# CoolerUI_SCH.net
KiCad netlist of a schematic drawn in Altium Designer
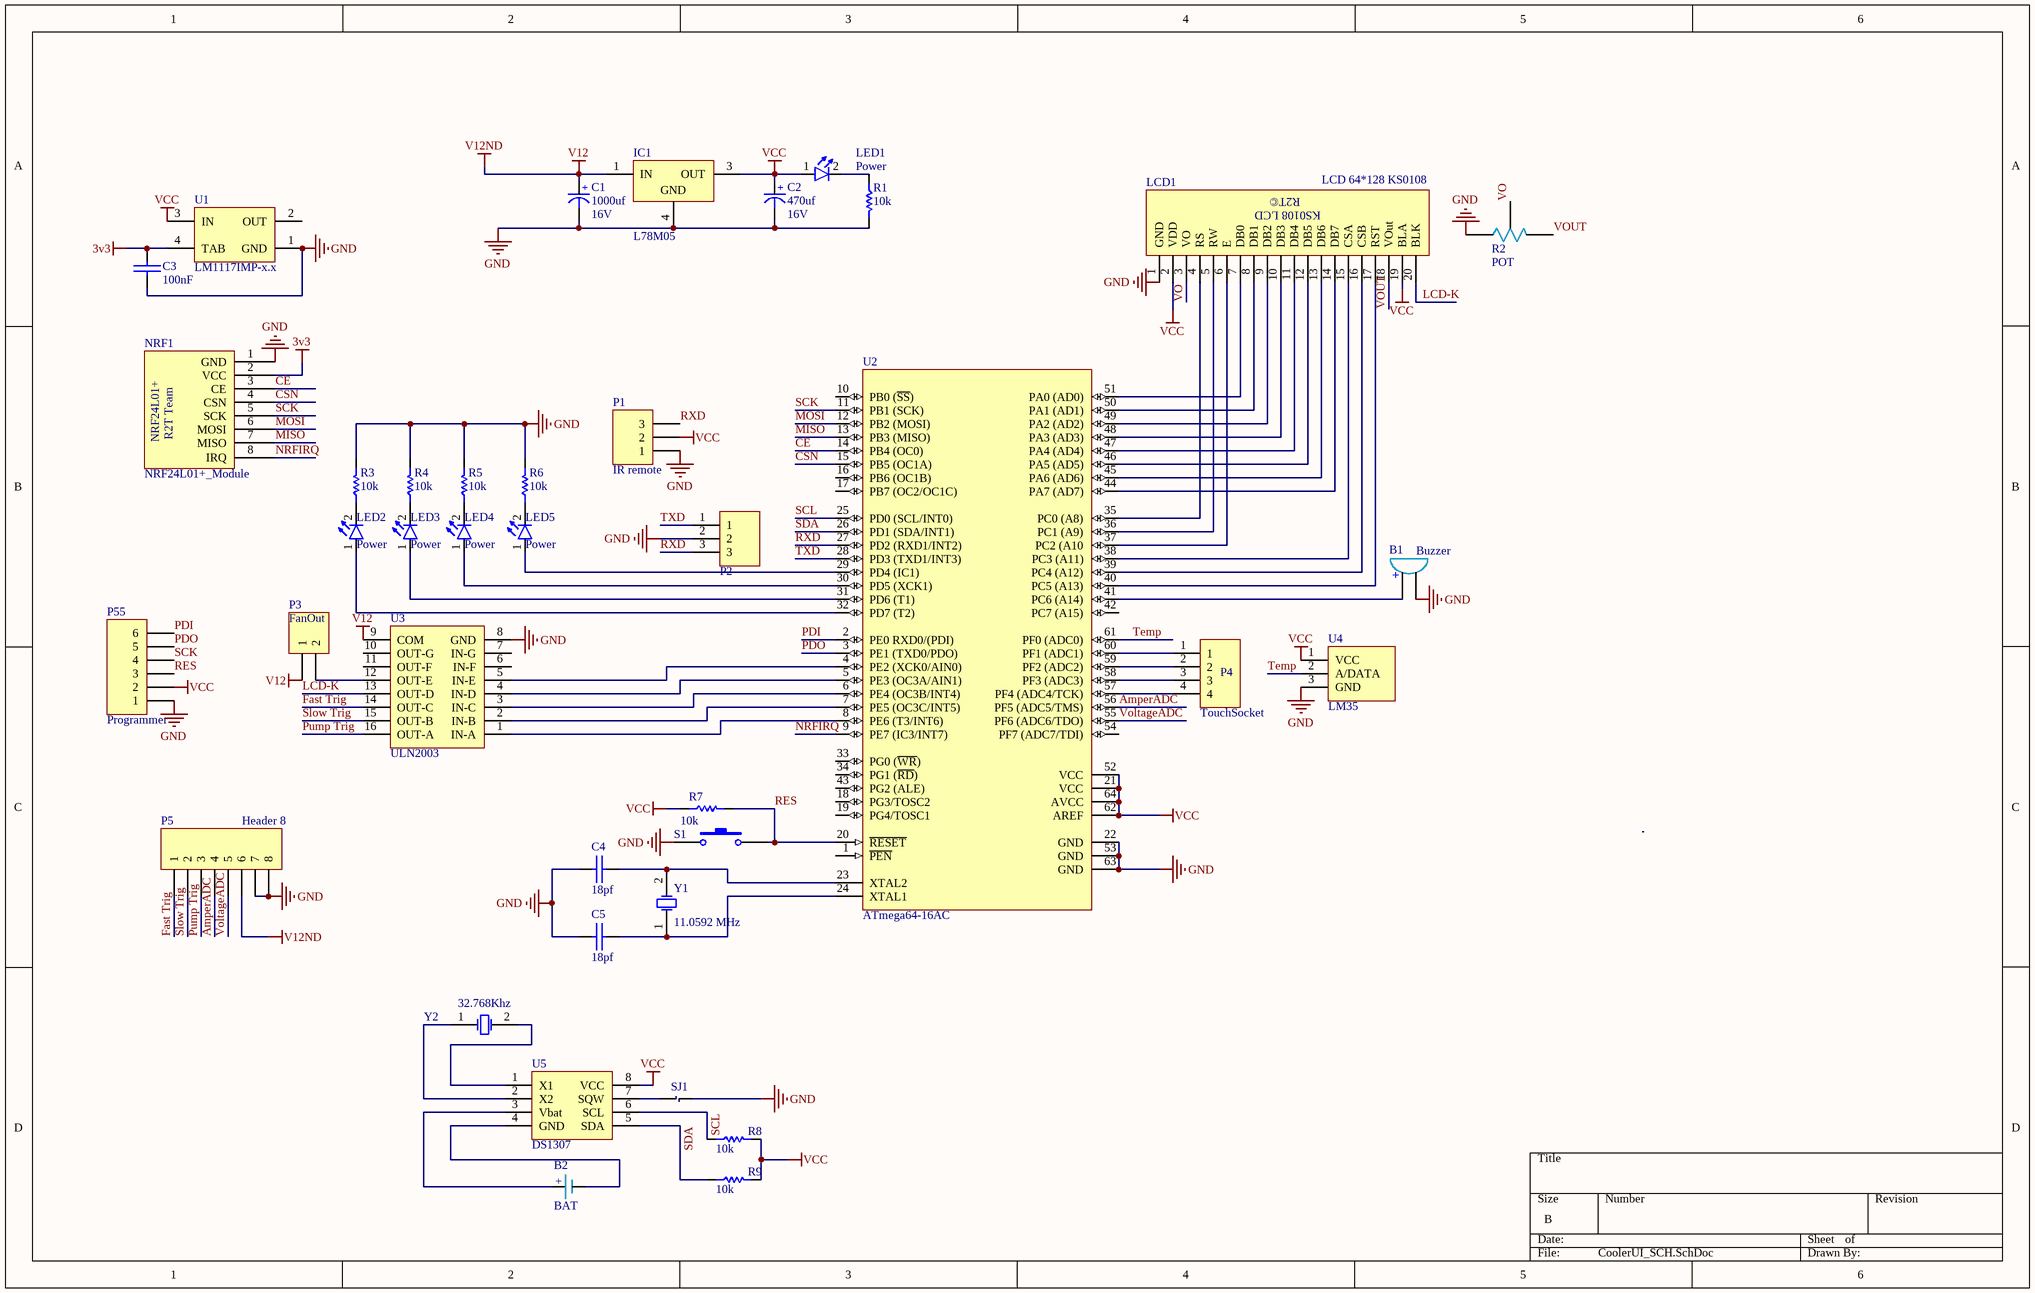
[diagram p0: CoolerUI_SCH.SchDoc]

(export (version "E")
  (design (tool "Eeschema 10.0.6"))
  (components
    (comp (ref "B1")
      (value "Buzzer")
      (footprint "Buzzer")
      (fields (field (name "DESIGNER") "Hamed Jafarzadeh"))
      (libsource (lib "R2T Team Library") (part "Buzzer"))
    )
    (comp (ref "B2") (value "BAT") (footprint "BAT_H") (libsource (lib "My_lib_new") (part "BAT")))
    (comp (ref "C1")
      (value "1000uf")
      (footprint "cap 04")
      (description "Polar Capacitor")
      (fields (field (name "VOLTAGE") "16V") (field (name "DESIGNER") "Saeid Jorablo"))
      (libsource (lib "My Library") (part "Cap-Polar"))
    )
    (comp (ref "C2")
      (value "470uf")
      (footprint "cap 03")
      (description "Polar Capacitor")
      (fields (field (name "VOLTAGE") "16V") (field (name "DESIGNER") "Saeid Jorablo"))
      (libsource (lib "My Library") (part "Cap-Polar"))
    )
    (comp (ref "C3")
      (value "100nF")
      (footprint "SMD_CAP_1206")
      (description "Bipolar Capacitor")
      (fields (field (name "VOLTAGE") "100V") (field (name "DESIGNER") "Saeid Jorablo"))
      (libsource (lib "My Library") (part "Cap-Bipolar"))
    )
    (comp (ref "C4")
      (value "18pf")
      (footprint "SMD_CAP_0805")
      (description "Bipolar Capacitor")
      (fields (field (name "VOLTAGE") "100V") (field (name "DESIGNER") "Saeid Jorablo"))
      (libsource (lib "My Library") (part "Cap-Bipolar"))
    )
    (comp (ref "C5")
      (value "18pf")
      (footprint "SMD_CAP_0805")
      (description "Bipolar Capacitor")
      (fields (field (name "VOLTAGE") "100V") (field (name "DESIGNER") "Saeid Jorablo"))
      (libsource (lib "My Library") (part "Cap-Bipolar"))
    )
    (comp (ref "IC1")
      (value "L78M05")
      (footprint "TO-252")
      (description "Precision 500mA Regulator")
      (libsource (lib "My Library") (part "L78M05"))
    )
    (comp (ref "LCD1")
      (value "LCD 64*128 KS0108")
      (footprint "KS0108 Graphical LCD")
      (libsource (lib "R2T Team Library") (part "LCD 64*128 KS0108"))
    )
    (comp (ref "LED1")
      (value "Power")
      (footprint "LED SMD 1206")
      (description "LED")
      (fields (field (name "COLOR") "Power") (field (name "DESIGNER") "Saeid Jorablo"))
      (libsource (lib "My Library") (part "LED"))
    )
    (comp (ref "LED2")
      (value "Power")
      (footprint "LED SMD 1206")
      (description "LED")
      (fields (field (name "COLOR") "Power") (field (name "DESIGNER") "Saeid Jorablo"))
      (libsource (lib "My Library") (part "LED"))
    )
    (comp (ref "LED3")
      (value "Power")
      (footprint "LED SMD 1206")
      (description "LED")
      (fields (field (name "COLOR") "Power") (field (name "DESIGNER") "Saeid Jorablo"))
      (libsource (lib "My Library") (part "LED"))
    )
    (comp (ref "LED4")
      (value "Power")
      (footprint "LED SMD 1206")
      (description "LED")
      (fields (field (name "COLOR") "Power") (field (name "DESIGNER") "Saeid Jorablo"))
      (libsource (lib "My Library") (part "LED"))
    )
    (comp (ref "LED5")
      (value "Power")
      (footprint "LED SMD 1206")
      (description "LED")
      (fields (field (name "COLOR") "Power") (field (name "DESIGNER") "Saeid Jorablo"))
      (libsource (lib "My Library") (part "LED"))
    )
    (comp (ref "NRF1")
      (value "NRF24L01+_Module")
      (footprint "NRF24L01+_Module")
      (fields (field (name "DESIGNER:") "HamedJafarzadeh"))
      (libsource (lib "R2T Team Library") (part "NRF24L01+_Module"))
    )
    (comp (ref "P1")
      (value "IR remote")
      (footprint "HDR1X3")
      (description "Header, 3-Pin")
      (fields (field (name "PUBLISHER") "Altium Limited"))
      (libsource (lib "Miscellaneous Connectors") (part "Header 3"))
    )
    (comp (ref "P2")
      (value "HWR")
      (footprint "Polarized Header 3")
      (fields (field (name "DESIGNER:") "Hamed Jafarzadeh - www.R2T.ir"))
      (libsource (lib "R2T Team Library") (part "3pin LHWR"))
    )
    (comp (ref "P3")
      (value "FanOut")
      (footprint "HDR1X2")
      (description "Header, 2-Pin")
      (fields (field (name "PUBLISHER") "Altium Limited"))
      (libsource (lib "Miscellaneous Connectors") (part "Header 2"))
    )
    (comp (ref "P4")
      (value "TouchSocket")
      (footprint "FPC,1mm,4way")
      (libsource (lib "R2T Team Library") (part "Header FPC 4pin"))
    )
    (comp (ref "P5")
      (value "Header 8")
      (footprint "HDR1X8")
      (description "Header, 8-Pin")
      (fields (field (name "PUBLISHER") "Altium Limited"))
      (libsource (lib "Miscellaneous Connectors") (part "Header 8"))
    )
    (comp (ref "P55")
      (value "Programmer")
      (footprint "HDR1X6")
      (description "Header, 6-Pin")
      (fields (field (name "PUBLISHER") "Altium Limited"))
      (libsource (lib "Miscellaneous Connectors") (part "Header 6"))
    )
    (comp (ref "R1")
      (value "10k")
      (footprint "RES 0805 (2012X06L)")
      (description "Resistor")
      (fields (field (name "TOLERANCE") "5%") (field (name "POWER") "1/8 W"))
      (libsource (lib "My Library") (part "Resistor"))
    )
    (comp (ref "R2") (value "POT") (footprint "MOL_1") (libsource (lib "My_lib_new") (part "POT")))
    (comp (ref "R3")
      (value "10k")
      (footprint "RES 0805 (2012X06L)")
      (description "Resistor")
      (fields (field (name "TOLERANCE") "5%") (field (name "POWER") "1/8 W"))
      (libsource (lib "My Library") (part "Resistor"))
    )
    (comp (ref "R4")
      (value "10k")
      (footprint "RES 0805 (2012X06L)")
      (description "Resistor")
      (fields (field (name "TOLERANCE") "5%") (field (name "POWER") "1/8 W"))
      (libsource (lib "My Library") (part "Resistor"))
    )
    (comp (ref "R5")
      (value "10k")
      (footprint "RES 0805 (2012X06L)")
      (description "Resistor")
      (fields (field (name "TOLERANCE") "5%") (field (name "POWER") "1/8 W"))
      (libsource (lib "My Library") (part "Resistor"))
    )
    (comp (ref "R6")
      (value "10k")
      (footprint "RES 0805 (2012X06L)")
      (description "Resistor")
      (fields (field (name "TOLERANCE") "5%") (field (name "POWER") "1/8 W"))
      (libsource (lib "My Library") (part "Resistor"))
    )
    (comp (ref "R7")
      (value "10k")
      (footprint "RES 0805 (2012X06L)")
      (description "Resistor")
      (fields (field (name "TOLERANCE") "5%") (field (name "POWER") "1/8 W"))
      (libsource (lib "My Library") (part "Resistor"))
    )
    (comp (ref "R8")
      (value "10k")
      (footprint "RES 0805 (2012X06L)")
      (description "Resistor")
      (libsource (lib "My Library") (part "Resistor"))
    )
    (comp (ref "R9")
      (value "10k")
      (footprint "RES 0805 (2012X06L)")
      (description "Resistor")
      (libsource (lib "My Library") (part "Resistor"))
    )
    (comp (ref "S1")
      (value "Switch PB SMD")
      (footprint "Switch PB SMD")
      (libsource (lib "R2T Team Library") (part "Switch PB SMD"))
    )
    (comp (ref "SJ1")
      (value "SmdJumper")
      (footprint "SMD Jumper")
      (libsource (lib "R2T Team Library") (part "SmdJumper"))
    )
    (comp (ref "U1")
      (value "LM1117IMP-x.x")
      (footprint "MP04A_N")
      (description "x.x Volt, 800mA Low-Dropout Linear Regulator, 4-pin SOT-223")
      (fields
        (field (name "PARTNUMBER") "LM1117IMP-3.3")
        (field (name "MANUFACTURER") "National Semiconductor")
        (field (name "PUBLISHER") "Altium Limited")
      )
      (libsource (lib "My Library") (part "LM1117IMP-x.x"))
    )
    (comp (ref "U2")
      (value "ATmega64-16AC")
      (footprint "64A_N")
      (description "8-Bit AVR Microcontroller with 64K Bytes of In-System Programmable Flash Memory")
      (fields (field (name "PUBLISHER") "Altium Limited"))
      (libsource (lib "Atmel Microcontroller 8-Bit AVR") (part "ATmega64-16AC"))
    )
    (comp (ref "U3") (value "ULN2003") (footprint "SO-16") (libsource (lib "My_lib_new") (part "ULN2003")))
    (comp (ref "U4") (value "LM35") (footprint "LM35") (libsource (lib "My_lib_new") (part "LM35")))
    (comp (ref "U5") (value "DS1307") (footprint "DIP8") (libsource (lib "My_lib_new") (part "DS1307")))
    (comp (ref "Y1")
      (value "11.0592 MHz")
      (footprint "Crystal SMD")
      (description "XTAL Crystal")
      (libsource (lib "My Library") (part "XTAL"))
    )
    (comp (ref "Y2")
      (value "32.768Khz")
      (footprint "XTAL RTC")
      (description "XTAL Crystal")
      (libsource (lib "My Library") (part "XTAL"))
    )
  )
  (nets
    (net (code "1") (name "/AmperADC") (class "Default")
      (node (ref "P5") (pin "4") (pinfunction "4_4") (pintype "passive"))
      (node (ref "U2") (pin "56") (pinfunction "PF5_(ADC5/TMS)_56") (pintype "bidirectional"))
    )
    (net (code "2") (name "/CE") (class "Default")
      (node (ref "NRF1") (pin "3") (pinfunction "CE_3") (pintype "passive"))
      (node (ref "U2") (pin "14") (pinfunction "PB4_(OC0)_14") (pintype "bidirectional"))
    )
    (net (code "3") (name "/CSN") (class "Default")
      (node (ref "NRF1") (pin "4") (pinfunction "CSN_4") (pintype "passive"))
      (node (ref "U2") (pin "15") (pinfunction "PB5_(OC1A)_15") (pintype "bidirectional"))
    )
    (net (code "4") (name "/Fast Trig") (class "Default")
      (node (ref "P5") (pin "1") (pinfunction "1_1") (pintype "passive"))
      (node (ref "U3") (pin "14") (pinfunction "OUT-C_14") (pintype "passive"))
    )
    (net (code "5") (name "/LCD-K") (class "Default")
      (node (ref "LCD1") (pin "20") (pinfunction "BLK_20") (pintype "passive"))
      (node (ref "U3") (pin "13") (pinfunction "OUT-D_13") (pintype "passive"))
    )
    (net (code "6") (name "/MISO") (class "Default")
      (node (ref "NRF1") (pin "7") (pinfunction "MISO_7") (pintype "passive"))
      (node (ref "U2") (pin "13") (pinfunction "PB3_(MISO)_13") (pintype "bidirectional"))
    )
    (net (code "7") (name "/MOSI") (class "Default")
      (node (ref "NRF1") (pin "6") (pinfunction "MOSI_6") (pintype "passive"))
      (node (ref "U2") (pin "12") (pinfunction "PB2_(MOSI)_12") (pintype "bidirectional"))
    )
    (net (code "8") (name "/NRFIRQ") (class "Default")
      (node (ref "NRF1") (pin "8") (pinfunction "IRQ_8") (pintype "passive"))
      (node (ref "U2") (pin "9") (pinfunction "PE7_(IC3/INT7)_9") (pintype "bidirectional"))
    )
    (net (code "9") (name "/PDI") (class "Default")
      (node (ref "P55") (pin "6") (pinfunction "6_6") (pintype "passive"))
      (node (ref "U2") (pin "2") (pinfunction "PE0_RXD0/(PDI)_2") (pintype "bidirectional"))
    )
    (net (code "10") (name "/PDO") (class "Default")
      (node (ref "P55") (pin "5") (pinfunction "5_5") (pintype "passive"))
      (node (ref "U2") (pin "3") (pinfunction "PE1_(TXD0/PDO)_3") (pintype "bidirectional"))
    )
    (net (code "11") (name "/Pump Trig") (class "Default")
      (node (ref "P5") (pin "3") (pinfunction "3_3") (pintype "passive"))
      (node (ref "U3") (pin "16") (pinfunction "OUT-A_16") (pintype "passive"))
    )
    (net (code "12") (name "/RES") (class "Default")
      (node (ref "P55") (pin "3") (pinfunction "3_3") (pintype "passive"))
      (node (ref "R7") (pin "2") (pinfunction "2_2") (pintype "passive"))
      (node (ref "S1") (pin "2") (pinfunction "2_2") (pintype "passive"))
      (node (ref "U2") (pin "20") (pinfunction "~{RESET}_20") (pintype "input"))
    )
    (net (code "13") (name "/RXD") (class "Default")
      (node (ref "P1") (pin "3") (pinfunction "3_3") (pintype "passive"))
      (node (ref "P2") (pin "3") (pinfunction "3_3") (pintype "passive"))
      (node (ref "U2") (pin "27") (pinfunction "PD2_(RXD1/INT2)_27") (pintype "bidirectional"))
    )
    (net (code "14") (name "/SCK") (class "Default")
      (node (ref "NRF1") (pin "5") (pinfunction "SCK_5") (pintype "passive"))
      (node (ref "P55") (pin "4") (pinfunction "4_4") (pintype "passive"))
      (node (ref "U2") (pin "11") (pinfunction "PB1_(SCK)_11") (pintype "bidirectional"))
    )
    (net (code "15") (name "/SCL") (class "Default")
      (node (ref "R8") (pin "1") (pinfunction "1_1") (pintype "passive"))
      (node (ref "U2") (pin "25") (pinfunction "PD0_(SCL/INT0)_25") (pintype "bidirectional"))
      (node (ref "U5") (pin "6") (pinfunction "SCL_6") (pintype "passive"))
    )
    (net (code "16") (name "/SDA") (class "Default")
      (node (ref "R9") (pin "1") (pinfunction "1_1") (pintype "passive"))
      (node (ref "U2") (pin "26") (pinfunction "PD1_(SDA/INT1)_26") (pintype "bidirectional"))
      (node (ref "U5") (pin "5") (pinfunction "SDA_5") (pintype "passive"))
    )
    (net (code "17") (name "/Slow Trig") (class "Default")
      (node (ref "P5") (pin "2") (pinfunction "2_2") (pintype "passive"))
      (node (ref "U3") (pin "15") (pinfunction "OUT-B_15") (pintype "passive"))
    )
    (net (code "18") (name "/TXD") (class "Default")
      (node (ref "P2") (pin "1") (pinfunction "1_1") (pintype "passive"))
      (node (ref "U2") (pin "28") (pinfunction "PD3_(TXD1/INT3)_28") (pintype "bidirectional"))
    )
    (net (code "19") (name "/Temp") (class "Default")
      (node (ref "U2") (pin "61") (pinfunction "PF0_(ADC0)_61") (pintype "bidirectional"))
      (node (ref "U4") (pin "2") (pinfunction "A/DATA_2") (pintype "passive"))
    )
    (net (code "20") (name "/VO") (class "Default")
      (node (ref "LCD1") (pin "3") (pinfunction "VO_3") (pintype "passive"))
      (node (ref "R2") (pin "2") (pintype "passive"))
    )
    (net (code "21") (name "/VOUT") (class "Default")
      (node (ref "LCD1") (pin "18") (pinfunction "VOut_18") (pintype "passive"))
      (node (ref "R2") (pin "3") (pintype "passive"))
    )
    (net (code "22") (name "/VoltageADC") (class "Default")
      (node (ref "P5") (pin "5") (pinfunction "5_5") (pintype "passive"))
      (node (ref "U2") (pin "55") (pinfunction "PF6_(ADC6/TDO)_55") (pintype "bidirectional"))
    )
    (net (code "23") (name "3v3") (class "Default")
      (node (ref "C3") (pin "1") (pinfunction "+_1") (pintype "passive"))
      (node (ref "NRF1") (pin "2") (pinfunction "VCC_2") (pintype "passive"))
      (node (ref "U1") (pin "4") (pinfunction "TAB_4") (pintype "power_in"))
    )
    (net (code "24") (name "GND") (class "Default")
      (node (ref "B1") (pin "2") (pinfunction "GND_2") (pintype "passive"))
      (node (ref "C1") (pin "2") (pinfunction "-_2") (pintype "passive"))
      (node (ref "C2") (pin "2") (pinfunction "-_2") (pintype "passive"))
      (node (ref "C3") (pin "2") (pinfunction "-_2") (pintype "passive"))
      (node (ref "C4") (pin "1") (pinfunction "+_1") (pintype "passive"))
      (node (ref "C5") (pin "1") (pinfunction "+_1") (pintype "passive"))
      (node (ref "IC1") (pin "4") (pinfunction "GND_4") (pintype "power_in"))
      (node (ref "LCD1") (pin "1") (pinfunction "GND_1") (pintype "passive"))
      (node (ref "NRF1") (pin "1") (pinfunction "GND_1") (pintype "passive"))
      (node (ref "P1") (pin "1") (pinfunction "1_1") (pintype "passive"))
      (node (ref "P2") (pin "2") (pinfunction "2_2") (pintype "passive"))
      (node (ref "P5") (pin "7") (pinfunction "7_7") (pintype "passive"))
      (node (ref "P5") (pin "8") (pinfunction "8_8") (pintype "passive"))
      (node (ref "P55") (pin "1") (pinfunction "1_1") (pintype "passive"))
      (node (ref "R1") (pin "2") (pinfunction "2_2") (pintype "passive"))
      (node (ref "R2") (pin "1") (pintype "passive"))
      (node (ref "R3") (pin "2") (pinfunction "2_2") (pintype "passive"))
      (node (ref "R4") (pin "2") (pinfunction "2_2") (pintype "passive"))
      (node (ref "R5") (pin "2") (pinfunction "2_2") (pintype "passive"))
      (node (ref "R6") (pin "2") (pinfunction "2_2") (pintype "passive"))
      (node (ref "S1") (pin "1") (pinfunction "1_1") (pintype "passive"))
      (node (ref "SJ1") (pin "2") (pinfunction "2_2") (pintype "passive"))
      (node (ref "U1") (pin "1") (pinfunction "GND_1") (pintype "power_in"))
      (node (ref "U2") (pin "22") (pinfunction "GND_22") (pintype "power_in"))
      (node (ref "U2") (pin "53") (pinfunction "GND_53") (pintype "power_in"))
      (node (ref "U2") (pin "63") (pinfunction "GND_63") (pintype "power_in"))
      (node (ref "U3") (pin "8") (pinfunction "GND_8") (pintype "passive"))
      (node (ref "U4") (pin "3") (pinfunction "GND_3") (pintype "passive"))
    )
    (net (code "25") (name "Net-(B1-VCC)") (class "Default")
      (node (ref "B1") (pin "1") (pinfunction "VCC_1") (pintype "passive"))
      (node (ref "U2") (pin "41") (pinfunction "PC6_(A14)_41") (pintype "bidirectional"))
    )
    (net (code "26") (name "Net-(C4--)") (class "Default")
      (node (ref "C4") (pin "2") (pinfunction "-_2") (pintype "passive"))
      (node (ref "U2") (pin "23") (pinfunction "XTAL2_23") (pintype "passive"))
      (node (ref "Y1") (pin "2") (pinfunction "OSC2_2") (pintype "passive"))
    )
    (net (code "27") (name "Net-(C5--)") (class "Default")
      (node (ref "C5") (pin "2") (pinfunction "-_2") (pintype "passive"))
      (node (ref "U2") (pin "24") (pinfunction "XTAL1_24") (pintype "passive"))
      (node (ref "Y1") (pin "1") (pinfunction "OSC1_1") (pintype "passive"))
    )
    (net (code "28") (name "Net-(LCD1-CSA)") (class "Default")
      (node (ref "LCD1") (pin "15") (pinfunction "CSA_15") (pintype "passive"))
      (node (ref "U2") (pin "38") (pinfunction "PC3_(A11)_38") (pintype "bidirectional"))
    )
    (net (code "29") (name "Net-(LCD1-CSB)") (class "Default")
      (node (ref "LCD1") (pin "16") (pinfunction "CSB_16") (pintype "passive"))
      (node (ref "U2") (pin "39") (pinfunction "PC4_(A12)_39") (pintype "bidirectional"))
    )
    (net (code "30") (name "Net-(LCD1-DB0)") (class "Default")
      (node (ref "LCD1") (pin "7") (pinfunction "DB0_7") (pintype "passive"))
      (node (ref "U2") (pin "51") (pinfunction "PA0_(AD0)_51") (pintype "bidirectional"))
    )
    (net (code "31") (name "Net-(LCD1-DB1)") (class "Default")
      (node (ref "LCD1") (pin "8") (pinfunction "DB1_8") (pintype "passive"))
      (node (ref "U2") (pin "50") (pinfunction "PA1_(AD1)_50") (pintype "bidirectional"))
    )
    (net (code "32") (name "Net-(LCD1-DB2)") (class "Default")
      (node (ref "LCD1") (pin "9") (pinfunction "DB2_9") (pintype "passive"))
      (node (ref "U2") (pin "49") (pinfunction "PA2_(AD2)_49") (pintype "bidirectional"))
    )
    (net (code "33") (name "Net-(LCD1-DB3)") (class "Default")
      (node (ref "LCD1") (pin "10") (pinfunction "DB3_10") (pintype "passive"))
      (node (ref "U2") (pin "48") (pinfunction "PA3_(AD3)_48") (pintype "bidirectional"))
    )
    (net (code "34") (name "Net-(LCD1-DB4)") (class "Default")
      (node (ref "LCD1") (pin "11") (pinfunction "DB4_11") (pintype "passive"))
      (node (ref "U2") (pin "47") (pinfunction "PA4_(AD4)_47") (pintype "bidirectional"))
    )
    (net (code "35") (name "Net-(LCD1-DB5)") (class "Default")
      (node (ref "LCD1") (pin "12") (pinfunction "DB5_12") (pintype "passive"))
      (node (ref "U2") (pin "46") (pinfunction "PA5_(AD5)_46") (pintype "bidirectional"))
    )
    (net (code "36") (name "Net-(LCD1-DB6)") (class "Default")
      (node (ref "LCD1") (pin "13") (pinfunction "DB6_13") (pintype "passive"))
      (node (ref "U2") (pin "45") (pinfunction "PA6_(AD6)_45") (pintype "bidirectional"))
    )
    (net (code "37") (name "Net-(LCD1-DB7)") (class "Default")
      (node (ref "LCD1") (pin "14") (pinfunction "DB7_14") (pintype "passive"))
      (node (ref "U2") (pin "44") (pinfunction "PA7_(AD7)_44") (pintype "bidirectional"))
    )
    (net (code "38") (name "Net-(LCD1-E)") (class "Default")
      (node (ref "LCD1") (pin "6") (pinfunction "E_6") (pintype "passive"))
      (node (ref "U2") (pin "37") (pinfunction "PC2_(A10_37") (pintype "bidirectional"))
    )
    (net (code "39") (name "Net-(LCD1-RS)") (class "Default")
      (node (ref "LCD1") (pin "4") (pinfunction "RS_4") (pintype "passive"))
      (node (ref "U2") (pin "35") (pinfunction "PC0_(A8)_35") (pintype "bidirectional"))
    )
    (net (code "40") (name "Net-(LCD1-RST)") (class "Default")
      (node (ref "LCD1") (pin "17") (pinfunction "RST_17") (pintype "passive"))
      (node (ref "U2") (pin "40") (pinfunction "PC5_(A13)_40") (pintype "bidirectional"))
    )
    (net (code "41") (name "Net-(LCD1-RW)") (class "Default")
      (node (ref "LCD1") (pin "5") (pinfunction "RW_5") (pintype "passive"))
      (node (ref "U2") (pin "36") (pinfunction "PC1_(A9)_36") (pintype "bidirectional"))
    )
    (net (code "42") (name "Net-(LED1-K)") (class "Default")
      (node (ref "LED1") (pin "2") (pinfunction "K_2") (pintype "passive"))
      (node (ref "R1") (pin "1") (pinfunction "1_1") (pintype "passive"))
    )
    (net (code "43") (name "Net-(LED2-A)") (class "Default")
      (node (ref "LED2") (pin "1") (pinfunction "A_1") (pintype "passive"))
      (node (ref "U2") (pin "32") (pinfunction "PD7_(T2)_32") (pintype "bidirectional"))
    )
    (net (code "44") (name "Net-(LED2-K)") (class "Default")
      (node (ref "LED2") (pin "2") (pinfunction "K_2") (pintype "passive"))
      (node (ref "R3") (pin "1") (pinfunction "1_1") (pintype "passive"))
    )
    (net (code "45") (name "Net-(LED3-A)") (class "Default")
      (node (ref "LED3") (pin "1") (pinfunction "A_1") (pintype "passive"))
      (node (ref "U2") (pin "31") (pinfunction "PD6_(T1)_31") (pintype "bidirectional"))
    )
    (net (code "46") (name "Net-(LED3-K)") (class "Default")
      (node (ref "LED3") (pin "2") (pinfunction "K_2") (pintype "passive"))
      (node (ref "R4") (pin "1") (pinfunction "1_1") (pintype "passive"))
    )
    (net (code "47") (name "Net-(LED4-A)") (class "Default")
      (node (ref "LED4") (pin "1") (pinfunction "A_1") (pintype "passive"))
      (node (ref "U2") (pin "30") (pinfunction "PD5_(XCK1)_30") (pintype "bidirectional"))
    )
    (net (code "48") (name "Net-(LED4-K)") (class "Default")
      (node (ref "LED4") (pin "2") (pinfunction "K_2") (pintype "passive"))
      (node (ref "R5") (pin "1") (pinfunction "1_1") (pintype "passive"))
    )
    (net (code "49") (name "Net-(LED5-A)") (class "Default")
      (node (ref "LED5") (pin "1") (pinfunction "A_1") (pintype "passive"))
      (node (ref "U2") (pin "29") (pinfunction "PD4_(IC1)_29") (pintype "bidirectional"))
    )
    (net (code "50") (name "Net-(LED5-K)") (class "Default")
      (node (ref "LED5") (pin "2") (pinfunction "K_2") (pintype "passive"))
      (node (ref "R6") (pin "1") (pinfunction "1_1") (pintype "passive"))
    )
    (net (code "51") (name "Net-(U2-PE2_(XCK0{slash}AIN0))") (class "Default")
      (node (ref "U2") (pin "4") (pinfunction "PE2_(XCK0/AIN0)_4") (pintype "bidirectional"))
      (node (ref "U3") (pin "5") (pinfunction "IN-E_5") (pintype "passive"))
    )
    (net (code "52") (name "Net-(U2-PE3_(OC3A{slash}AIN1))") (class "Default")
      (node (ref "U2") (pin "5") (pinfunction "PE3_(OC3A/AIN1)_5") (pintype "bidirectional"))
      (node (ref "U3") (pin "4") (pinfunction "IN-D_4") (pintype "passive"))
    )
    (net (code "53") (name "Net-(U2-PE4_(OC3B{slash}INT4))") (class "Default")
      (node (ref "U2") (pin "6") (pinfunction "PE4_(OC3B/INT4)_6") (pintype "bidirectional"))
      (node (ref "U3") (pin "3") (pinfunction "IN-C_3") (pintype "passive"))
    )
    (net (code "54") (name "Net-(U2-PE5_(OC3C{slash}INT5))") (class "Default")
      (node (ref "U2") (pin "7") (pinfunction "PE5_(OC3C/INT5)_7") (pintype "bidirectional"))
      (node (ref "U3") (pin "2") (pinfunction "IN-B_2") (pintype "passive"))
    )
    (net (code "55") (name "Net-(U2-PE6_(T3{slash}INT6))") (class "Default")
      (node (ref "U2") (pin "8") (pinfunction "PE6_(T3/INT6)_8") (pintype "bidirectional"))
      (node (ref "U3") (pin "1") (pinfunction "IN-A_1") (pintype "passive"))
    )
    (net (code "56") (name "Net-(U2-PF1_(ADC1))") (class "Default")
      (node (ref "P4") (pin "1") (pinfunction "1_1") (pintype "passive"))
      (node (ref "U2") (pin "60") (pinfunction "PF1_(ADC1)_60") (pintype "bidirectional"))
    )
    (net (code "57") (name "Net-(U2-PF2_(ADC2))") (class "Default")
      (node (ref "P4") (pin "2") (pinfunction "2_2") (pintype "passive"))
      (node (ref "U2") (pin "59") (pinfunction "PF2_(ADC2)_59") (pintype "bidirectional"))
    )
    (net (code "58") (name "Net-(U2-PF3_(ADC3))") (class "Default")
      (node (ref "P4") (pin "3") (pinfunction "3_3") (pintype "passive"))
      (node (ref "U2") (pin "58") (pinfunction "PF3_(ADC3)_58") (pintype "bidirectional"))
    )
    (net (code "59") (name "Net-(U2-PF4_(ADC4{slash}TCK))") (class "Default")
      (node (ref "P4") (pin "4") (pinfunction "4_4") (pintype "passive"))
      (node (ref "U2") (pin "57") (pinfunction "PF4_(ADC4/TCK)_57") (pintype "bidirectional"))
    )
    (net (code "60") (name "Net-(U3-OUT-E)") (class "Default")
      (node (ref "P3") (pin "2") (pinfunction "2_2") (pintype "passive"))
      (node (ref "U3") (pin "12") (pinfunction "OUT-E_12") (pintype "passive"))
    )
    (net (code "61") (name "Net-(U5-GND)") (class "Default")
      (node (ref "B2") (pin "2") (pintype "passive"))
      (node (ref "U5") (pin "4") (pinfunction "GND_4") (pintype "passive"))
    )
    (net (code "62") (name "Net-(U5-SQW)") (class "Default")
      (node (ref "SJ1") (pin "1") (pintype "passive"))
      (node (ref "U5") (pin "7") (pinfunction "SQW_7") (pintype "passive"))
    )
    (net (code "63") (name "Net-(U5-Vbat)") (class "Default")
      (node (ref "B2") (pin "1") (pintype "passive"))
      (node (ref "U5") (pin "3") (pinfunction "Vbat_3") (pintype "passive"))
    )
    (net (code "64") (name "Net-(U5-X1)") (class "Default")
      (node (ref "U5") (pin "1") (pinfunction "X1_1") (pintype "passive"))
      (node (ref "Y2") (pin "2") (pinfunction "OSC2_2") (pintype "passive"))
    )
    (net (code "65") (name "Net-(U5-X2)") (class "Default")
      (node (ref "U5") (pin "2") (pinfunction "X2_2") (pintype "passive"))
      (node (ref "Y2") (pin "1") (pinfunction "OSC1_1") (pintype "passive"))
    )
    (net (code "66") (name "V12") (class "Default")
      (node (ref "C1") (pin "1") (pinfunction "+_1") (pintype "passive"))
      (node (ref "IC1") (pin "1") (pinfunction "IN_1") (pintype "power_in"))
      (node (ref "P3") (pin "1") (pinfunction "1_1") (pintype "passive"))
      (node (ref "P5") (pin "6") (pinfunction "6_6") (pintype "passive"))
      (node (ref "U3") (pin "9") (pinfunction "COM_9") (pintype "passive"))
    )
    (net (code "67") (name "VCC") (class "Default")
      (node (ref "C2") (pin "1") (pinfunction "+_1") (pintype "passive"))
      (node (ref "IC1") (pin "3") (pinfunction "OUT_3") (pintype "power_in"))
      (node (ref "LCD1") (pin "19") (pinfunction "BLA_19") (pintype "passive"))
      (node (ref "LCD1") (pin "2") (pinfunction "VDD_2") (pintype "passive"))
      (node (ref "LED1") (pin "1") (pinfunction "A_1") (pintype "passive"))
      (node (ref "P1") (pin "2") (pinfunction "2_2") (pintype "passive"))
      (node (ref "P55") (pin "2") (pinfunction "2_2") (pintype "passive"))
      (node (ref "R7") (pin "1") (pinfunction "1_1") (pintype "passive"))
      (node (ref "R8") (pin "2") (pinfunction "2_2") (pintype "passive"))
      (node (ref "R9") (pin "2") (pinfunction "2_2") (pintype "passive"))
      (node (ref "U1") (pin "3") (pinfunction "IN_3") (pintype "power_in"))
      (node (ref "U2") (pin "21") (pinfunction "VCC_21") (pintype "power_in"))
      (node (ref "U2") (pin "52") (pinfunction "VCC_52") (pintype "power_in"))
      (node (ref "U2") (pin "62") (pinfunction "AREF_62") (pintype "passive"))
      (node (ref "U2") (pin "64") (pinfunction "AVCC_64") (pintype "power_in"))
      (node (ref "U4") (pin "1") (pinfunction "VCC_1") (pintype "passive"))
      (node (ref "U5") (pin "8") (pinfunction "VCC_8") (pintype "passive"))
    )
    (net (code "68") (name "unconnected-(U1-OUT-Pad2)") (class "Default")
      (node (ref "U1") (pin "2") (pinfunction "OUT_2") (pintype "power_in"))
    )
    (net (code "69") (name "unconnected-(U2-PB0_(~{SS})-Pad10)") (class "Default")
      (node (ref "U2") (pin "10") (pinfunction "PB0_(~{SS})_10") (pintype "bidirectional"))
    )
    (net (code "70") (name "unconnected-(U2-PB6_(OC1B)-Pad16)") (class "Default")
      (node (ref "U2") (pin "16") (pinfunction "PB6_(OC1B)_16") (pintype "bidirectional"))
    )
    (net (code "71") (name "unconnected-(U2-PB7_(OC2{slash}OC1C)-Pad17)") (class "Default")
      (node (ref "U2") (pin "17") (pinfunction "PB7_(OC2/OC1C)_17") (pintype "bidirectional"))
    )
    (net (code "72") (name "unconnected-(U2-PC7_(A15)-Pad42)") (class "Default")
      (node (ref "U2") (pin "42") (pinfunction "PC7_(A15)_42") (pintype "bidirectional"))
    )
    (net (code "73") (name "unconnected-(U2-PF7_(ADC7{slash}TDI)-Pad54)") (class "Default")
      (node (ref "U2") (pin "54") (pinfunction "PF7_(ADC7/TDI)_54") (pintype "bidirectional"))
    )
    (net (code "74") (name "unconnected-(U2-PG0_(~{WR})-Pad33)") (class "Default")
      (node (ref "U2") (pin "33") (pinfunction "PG0_(~{WR})_33") (pintype "bidirectional"))
    )
    (net (code "75") (name "unconnected-(U2-PG1_(~{RD})-Pad34)") (class "Default")
      (node (ref "U2") (pin "34") (pinfunction "PG1_(~{RD})_34") (pintype "bidirectional"))
    )
    (net (code "76") (name "unconnected-(U2-PG2_(ALE)-Pad43)") (class "Default")
      (node (ref "U2") (pin "43") (pinfunction "PG2_(ALE)_43") (pintype "bidirectional"))
    )
    (net (code "77") (name "unconnected-(U2-PG3{slash}TOSC2-Pad18)") (class "Default")
      (node (ref "U2") (pin "18") (pinfunction "PG3/TOSC2_18") (pintype "bidirectional"))
    )
    (net (code "78") (name "unconnected-(U2-PG4{slash}TOSC1-Pad19)") (class "Default")
      (node (ref "U2") (pin "19") (pinfunction "PG4/TOSC1_19") (pintype "bidirectional"))
    )
    (net (code "79") (name "unconnected-(U2-~{PEN}-Pad1)") (class "Default")
      (node (ref "U2") (pin "1") (pinfunction "~{PEN}_1") (pintype "input"))
    )
    (net (code "80") (name "unconnected-(U3-IN-F-Pad6)") (class "Default")
      (node (ref "U3") (pin "6") (pinfunction "IN-F_6") (pintype "passive"))
    )
    (net (code "81") (name "unconnected-(U3-IN-G-Pad7)") (class "Default")
      (node (ref "U3") (pin "7") (pinfunction "IN-G_7") (pintype "passive"))
    )
    (net (code "82") (name "unconnected-(U3-OUT-F-Pad11)") (class "Default")
      (node (ref "U3") (pin "11") (pinfunction "OUT-F_11") (pintype "passive"))
    )
    (net (code "83") (name "unconnected-(U3-OUT-G-Pad10)") (class "Default")
      (node (ref "U3") (pin "10") (pinfunction "OUT-G_10") (pintype "passive"))
    )
  )
)
